# Adafruit_NeoPixel_Ring_24.net
KiCad netlist of a schematic drawn in EAGLE
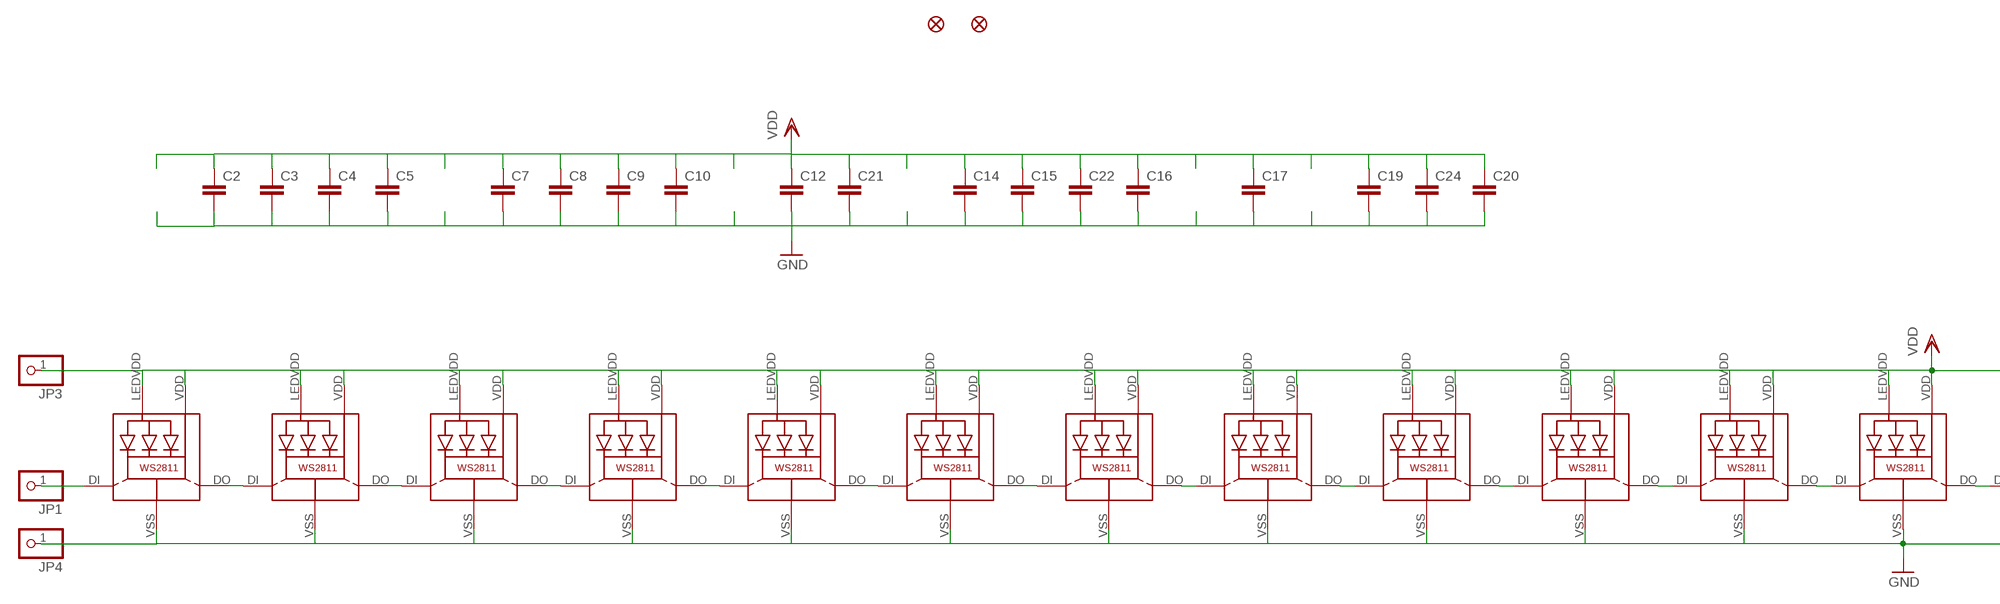
[diagram p0: schematic, sheet 1, part 1 of 2]
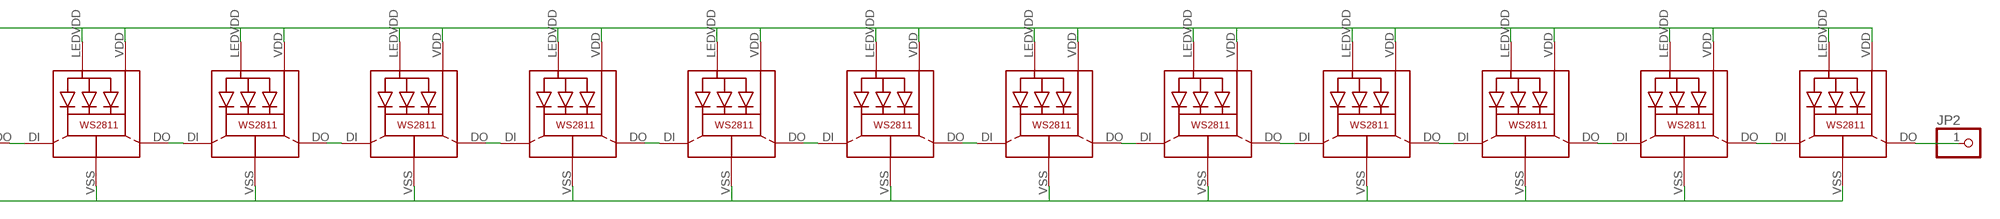
[diagram p1: schematic, sheet 1, part 2 of 2]

(export (version "E")
  (design (tool "Eeschema 10.0.6"))
  (components
    (comp (ref "C2")
      (value "C-EUC0603")
      (footprint "eagle-import:C0603")
      (libsource (lib "eagle-import") (part "C-EUC0603"))
    )
    (comp (ref "C3")
      (value "C-EUC0603")
      (footprint "eagle-import:C0603")
      (libsource (lib "eagle-import") (part "C-EUC0603"))
    )
    (comp (ref "C4")
      (value "C-EUC0603")
      (footprint "eagle-import:C0603")
      (libsource (lib "eagle-import") (part "C-EUC0603"))
    )
    (comp (ref "C5")
      (value "C-EUC0603")
      (footprint "eagle-import:C0603")
      (libsource (lib "eagle-import") (part "C-EUC0603"))
    )
    (comp (ref "C7")
      (value "C-EUC0603")
      (footprint "eagle-import:C0603")
      (libsource (lib "eagle-import") (part "C-EUC0603"))
    )
    (comp (ref "C8")
      (value "C-EUC0603")
      (footprint "eagle-import:C0603")
      (libsource (lib "eagle-import") (part "C-EUC0603"))
    )
    (comp (ref "C9")
      (value "C-EUC0603")
      (footprint "eagle-import:C0603")
      (libsource (lib "eagle-import") (part "C-EUC0603"))
    )
    (comp (ref "C10")
      (value "C-EUC0603")
      (footprint "eagle-import:C0603")
      (libsource (lib "eagle-import") (part "C-EUC0603"))
    )
    (comp (ref "C12")
      (value "C-EUC0603")
      (footprint "eagle-import:C0603")
      (libsource (lib "eagle-import") (part "C-EUC0603"))
    )
    (comp (ref "C14")
      (value "C-EUC0603")
      (footprint "eagle-import:C0603")
      (libsource (lib "eagle-import") (part "C-EUC0603"))
    )
    (comp (ref "C15")
      (value "C-EUC0603")
      (footprint "eagle-import:C0603")
      (libsource (lib "eagle-import") (part "C-EUC0603"))
    )
    (comp (ref "C16")
      (value "C-EUC0603")
      (footprint "eagle-import:C0603")
      (libsource (lib "eagle-import") (part "C-EUC0603"))
    )
    (comp (ref "C17")
      (value "C-EUC0603")
      (footprint "eagle-import:C0603")
      (libsource (lib "eagle-import") (part "C-EUC0603"))
    )
    (comp (ref "C19")
      (value "C-EUC0603")
      (footprint "eagle-import:C0603")
      (libsource (lib "eagle-import") (part "C-EUC0603"))
    )
    (comp (ref "C20")
      (value "C-EUC0603")
      (footprint "eagle-import:C0603")
      (libsource (lib "eagle-import") (part "C-EUC0603"))
    )
    (comp (ref "C21")
      (value "C-EUC0603")
      (footprint "eagle-import:C0603")
      (libsource (lib "eagle-import") (part "C-EUC0603"))
    )
    (comp (ref "C22")
      (value "C-EUC0603")
      (footprint "eagle-import:C0603")
      (libsource (lib "eagle-import") (part "C-EUC0603"))
    )
    (comp (ref "C24")
      (value "C-EUC0603")
      (footprint "eagle-import:C0603")
      (libsource (lib "eagle-import") (part "C-EUC0603"))
    )
    (comp (ref "FID1")
      (value "FIDUCIAL\"\"")
      (footprint "eagle-import:FIDUCIAL_1MM")
      (libsource (lib "eagle-import") (part "FIDUCIAL{dblquote}{dblquote}"))
    )
    (comp (ref "FID2")
      (value "FIDUCIAL\"\"")
      (footprint "eagle-import:FIDUCIAL_1MM")
      (libsource (lib "eagle-import") (part "FIDUCIAL{dblquote}{dblquote}"))
    )
    (comp (ref "JP1")
      (value "PINHD-1X1CB")
      (footprint "eagle-import:1X01-CLEANBIG")
      (libsource (lib "eagle-import") (part "PINHD-1X1CB"))
    )
    (comp (ref "JP2")
      (value "PINHD-1X1CB")
      (footprint "eagle-import:1X01-CLEANBIG")
      (libsource (lib "eagle-import") (part "PINHD-1X1CB"))
    )
    (comp (ref "JP3")
      (value "PINHD-1X1CB")
      (footprint "eagle-import:1X01-CLEANBIG")
      (libsource (lib "eagle-import") (part "PINHD-1X1CB"))
    )
    (comp (ref "JP4")
      (value "PINHD-1X1CB")
      (footprint "eagle-import:1X01-CLEANBIG")
      (libsource (lib "eagle-import") (part "PINHD-1X1CB"))
    )
    (comp (ref "LED1")
      (value "WS28115050")
      (footprint "eagle-import:WS28115050")
      (libsource (lib "eagle-import") (part "WS28115050"))
    )
    (comp (ref "LED2")
      (value "WS28115050")
      (footprint "eagle-import:WS28115050")
      (libsource (lib "eagle-import") (part "WS28115050"))
    )
    (comp (ref "LED3")
      (value "WS28115050")
      (footprint "eagle-import:WS28115050")
      (libsource (lib "eagle-import") (part "WS28115050"))
    )
    (comp (ref "LED4")
      (value "WS28115050")
      (footprint "eagle-import:WS28115050")
      (libsource (lib "eagle-import") (part "WS28115050"))
    )
    (comp (ref "LED5")
      (value "WS28115050")
      (footprint "eagle-import:WS28115050")
      (libsource (lib "eagle-import") (part "WS28115050"))
    )
    (comp (ref "LED6")
      (value "WS28115050")
      (footprint "eagle-import:WS28115050")
      (libsource (lib "eagle-import") (part "WS28115050"))
    )
    (comp (ref "LED7")
      (value "WS28115050")
      (footprint "eagle-import:WS28115050")
      (libsource (lib "eagle-import") (part "WS28115050"))
    )
    (comp (ref "LED8")
      (value "WS28115050")
      (footprint "eagle-import:WS28115050")
      (libsource (lib "eagle-import") (part "WS28115050"))
    )
    (comp (ref "LED9")
      (value "WS28115050")
      (footprint "eagle-import:WS28115050")
      (libsource (lib "eagle-import") (part "WS28115050"))
    )
    (comp (ref "LED10")
      (value "WS28115050")
      (footprint "eagle-import:WS28115050")
      (libsource (lib "eagle-import") (part "WS28115050"))
    )
    (comp (ref "LED11")
      (value "WS28115050")
      (footprint "eagle-import:WS28115050")
      (libsource (lib "eagle-import") (part "WS28115050"))
    )
    (comp (ref "LED12")
      (value "WS28115050")
      (footprint "eagle-import:WS28115050")
      (libsource (lib "eagle-import") (part "WS28115050"))
    )
    (comp (ref "LED13")
      (value "WS28115050")
      (footprint "eagle-import:WS28115050")
      (libsource (lib "eagle-import") (part "WS28115050"))
    )
    (comp (ref "LED14")
      (value "WS28115050")
      (footprint "eagle-import:WS28115050")
      (libsource (lib "eagle-import") (part "WS28115050"))
    )
    (comp (ref "LED15")
      (value "WS28115050")
      (footprint "eagle-import:WS28115050")
      (libsource (lib "eagle-import") (part "WS28115050"))
    )
    (comp (ref "LED16")
      (value "WS28115050")
      (footprint "eagle-import:WS28115050")
      (libsource (lib "eagle-import") (part "WS28115050"))
    )
    (comp (ref "LED17")
      (value "WS28115050")
      (footprint "eagle-import:WS28115050")
      (libsource (lib "eagle-import") (part "WS28115050"))
    )
    (comp (ref "LED18")
      (value "WS28115050")
      (footprint "eagle-import:WS28115050")
      (libsource (lib "eagle-import") (part "WS28115050"))
    )
    (comp (ref "LED19")
      (value "WS28115050")
      (footprint "eagle-import:WS28115050")
      (libsource (lib "eagle-import") (part "WS28115050"))
    )
    (comp (ref "LED20")
      (value "WS28115050")
      (footprint "eagle-import:WS28115050")
      (libsource (lib "eagle-import") (part "WS28115050"))
    )
    (comp (ref "LED21")
      (value "WS28115050")
      (footprint "eagle-import:WS28115050")
      (libsource (lib "eagle-import") (part "WS28115050"))
    )
    (comp (ref "LED22")
      (value "WS28115050")
      (footprint "eagle-import:WS28115050")
      (libsource (lib "eagle-import") (part "WS28115050"))
    )
    (comp (ref "LED23")
      (value "WS28115050")
      (footprint "eagle-import:WS28115050")
      (libsource (lib "eagle-import") (part "WS28115050"))
    )
    (comp (ref "LED24")
      (value "WS28115050")
      (footprint "eagle-import:WS28115050")
      (libsource (lib "eagle-import") (part "WS28115050"))
    )
  )
  (nets
    (net (code "1") (name "GND") (class "Default")
      (node (ref "C10") (pin "2") (pinfunction "2_2") (pintype "passive"))
      (node (ref "C12") (pin "2") (pinfunction "2_2") (pintype "passive"))
      (node (ref "C14") (pin "2") (pinfunction "2_2") (pintype "passive"))
      (node (ref "C15") (pin "2") (pinfunction "2_2") (pintype "passive"))
      (node (ref "C16") (pin "2") (pinfunction "2_2") (pintype "passive"))
      (node (ref "C17") (pin "2") (pinfunction "2_2") (pintype "passive"))
      (node (ref "C19") (pin "2") (pinfunction "2_2") (pintype "passive"))
      (node (ref "C2") (pin "2") (pinfunction "2_2") (pintype "passive"))
      (node (ref "C20") (pin "2") (pinfunction "2_2") (pintype "passive"))
      (node (ref "C21") (pin "2") (pinfunction "2_2") (pintype "passive"))
      (node (ref "C22") (pin "2") (pinfunction "2_2") (pintype "passive"))
      (node (ref "C24") (pin "2") (pinfunction "2_2") (pintype "passive"))
      (node (ref "C3") (pin "2") (pinfunction "2_2") (pintype "passive"))
      (node (ref "C4") (pin "2") (pinfunction "2_2") (pintype "passive"))
      (node (ref "C5") (pin "2") (pinfunction "2_2") (pintype "passive"))
      (node (ref "C7") (pin "2") (pinfunction "2_2") (pintype "passive"))
      (node (ref "C8") (pin "2") (pinfunction "2_2") (pintype "passive"))
      (node (ref "C9") (pin "2") (pinfunction "2_2") (pintype "passive"))
      (node (ref "JP4") (pin "1") (pinfunction "1_1") (pintype "passive"))
      (node (ref "LED1") (pin "VSS") (pinfunction "GND_VSS") (pintype "power_in"))
      (node (ref "LED10") (pin "VSS") (pinfunction "GND_VSS") (pintype "power_in"))
      (node (ref "LED11") (pin "VSS") (pinfunction "GND_VSS") (pintype "power_in"))
      (node (ref "LED12") (pin "VSS") (pinfunction "GND_VSS") (pintype "power_in"))
      (node (ref "LED13") (pin "VSS") (pinfunction "GND_VSS") (pintype "power_in"))
      (node (ref "LED14") (pin "VSS") (pinfunction "GND_VSS") (pintype "power_in"))
      (node (ref "LED15") (pin "VSS") (pinfunction "GND_VSS") (pintype "power_in"))
      (node (ref "LED16") (pin "VSS") (pinfunction "GND_VSS") (pintype "power_in"))
      (node (ref "LED17") (pin "VSS") (pinfunction "GND_VSS") (pintype "power_in"))
      (node (ref "LED18") (pin "VSS") (pinfunction "GND_VSS") (pintype "power_in"))
      (node (ref "LED19") (pin "VSS") (pinfunction "GND_VSS") (pintype "power_in"))
      (node (ref "LED2") (pin "VSS") (pinfunction "GND_VSS") (pintype "power_in"))
      (node (ref "LED20") (pin "VSS") (pinfunction "GND_VSS") (pintype "power_in"))
      (node (ref "LED21") (pin "VSS") (pinfunction "GND_VSS") (pintype "power_in"))
      (node (ref "LED22") (pin "VSS") (pinfunction "GND_VSS") (pintype "power_in"))
      (node (ref "LED23") (pin "VSS") (pinfunction "GND_VSS") (pintype "power_in"))
      (node (ref "LED24") (pin "VSS") (pinfunction "GND_VSS") (pintype "power_in"))
      (node (ref "LED3") (pin "VSS") (pinfunction "GND_VSS") (pintype "power_in"))
      (node (ref "LED4") (pin "VSS") (pinfunction "GND_VSS") (pintype "power_in"))
      (node (ref "LED5") (pin "VSS") (pinfunction "GND_VSS") (pintype "power_in"))
      (node (ref "LED6") (pin "VSS") (pinfunction "GND_VSS") (pintype "power_in"))
      (node (ref "LED7") (pin "VSS") (pinfunction "GND_VSS") (pintype "power_in"))
      (node (ref "LED8") (pin "VSS") (pinfunction "GND_VSS") (pintype "power_in"))
      (node (ref "LED9") (pin "VSS") (pinfunction "GND_VSS") (pintype "power_in"))
    )
    (net (code "2") (name "Net-(JP1-Pad1)") (class "Default")
      (node (ref "JP1") (pin "1") (pinfunction "1_1") (pintype "passive"))
      (node (ref "LED1") (pin "DI") (pinfunction "DI_DI") (pintype "input"))
    )
    (net (code "3") (name "Net-(JP2-Pad1)") (class "Default")
      (node (ref "JP2") (pin "1") (pinfunction "1_1") (pintype "passive"))
      (node (ref "LED24") (pin "DO") (pinfunction "DO_DO") (pintype "output"))
    )
    (net (code "4") (name "Net-(LED1-PadDO)") (class "Default")
      (node (ref "LED1") (pin "DO") (pinfunction "DO_DO") (pintype "output"))
      (node (ref "LED2") (pin "DI") (pinfunction "DI_DI") (pintype "input"))
    )
    (net (code "5") (name "Net-(LED2-PadDO)") (class "Default")
      (node (ref "LED2") (pin "DO") (pinfunction "DO_DO") (pintype "output"))
      (node (ref "LED3") (pin "DI") (pinfunction "DI_DI") (pintype "input"))
    )
    (net (code "6") (name "Net-(LED3-PadDO)") (class "Default")
      (node (ref "LED3") (pin "DO") (pinfunction "DO_DO") (pintype "output"))
      (node (ref "LED4") (pin "DI") (pinfunction "DI_DI") (pintype "input"))
    )
    (net (code "7") (name "Net-(LED4-PadDO)") (class "Default")
      (node (ref "LED4") (pin "DO") (pinfunction "DO_DO") (pintype "output"))
      (node (ref "LED5") (pin "DI") (pinfunction "DI_DI") (pintype "input"))
    )
    (net (code "8") (name "Net-(LED5-PadDO)") (class "Default")
      (node (ref "LED5") (pin "DO") (pinfunction "DO_DO") (pintype "output"))
      (node (ref "LED6") (pin "DI") (pinfunction "DI_DI") (pintype "input"))
    )
    (net (code "9") (name "Net-(LED6-PadDO)") (class "Default")
      (node (ref "LED6") (pin "DO") (pinfunction "DO_DO") (pintype "output"))
      (node (ref "LED7") (pin "DI") (pinfunction "DI_DI") (pintype "input"))
    )
    (net (code "10") (name "Net-(LED7-PadDO)") (class "Default")
      (node (ref "LED7") (pin "DO") (pinfunction "DO_DO") (pintype "output"))
      (node (ref "LED8") (pin "DI") (pinfunction "DI_DI") (pintype "input"))
    )
    (net (code "11") (name "Net-(LED8-PadDO)") (class "Default")
      (node (ref "LED8") (pin "DO") (pinfunction "DO_DO") (pintype "output"))
      (node (ref "LED9") (pin "DI") (pinfunction "DI_DI") (pintype "input"))
    )
    (net (code "12") (name "Net-(LED10-PadDI)") (class "Default")
      (node (ref "LED10") (pin "DI") (pinfunction "DI_DI") (pintype "input"))
      (node (ref "LED9") (pin "DO") (pinfunction "DO_DO") (pintype "output"))
    )
    (net (code "13") (name "Net-(LED10-PadDO)") (class "Default")
      (node (ref "LED10") (pin "DO") (pinfunction "DO_DO") (pintype "output"))
      (node (ref "LED11") (pin "DI") (pinfunction "DI_DI") (pintype "input"))
    )
    (net (code "14") (name "Net-(LED11-PadDO)") (class "Default")
      (node (ref "LED11") (pin "DO") (pinfunction "DO_DO") (pintype "output"))
      (node (ref "LED12") (pin "DI") (pinfunction "DI_DI") (pintype "input"))
    )
    (net (code "15") (name "Net-(LED12-PadDO)") (class "Default")
      (node (ref "LED12") (pin "DO") (pinfunction "DO_DO") (pintype "output"))
      (node (ref "LED13") (pin "DI") (pinfunction "DI_DI") (pintype "input"))
    )
    (net (code "16") (name "Net-(LED13-PadDO)") (class "Default")
      (node (ref "LED13") (pin "DO") (pinfunction "DO_DO") (pintype "output"))
      (node (ref "LED14") (pin "DI") (pinfunction "DI_DI") (pintype "input"))
    )
    (net (code "17") (name "Net-(LED14-PadDO)") (class "Default")
      (node (ref "LED14") (pin "DO") (pinfunction "DO_DO") (pintype "output"))
      (node (ref "LED15") (pin "DI") (pinfunction "DI_DI") (pintype "input"))
    )
    (net (code "18") (name "Net-(LED15-PadDO)") (class "Default")
      (node (ref "LED15") (pin "DO") (pinfunction "DO_DO") (pintype "output"))
      (node (ref "LED16") (pin "DI") (pinfunction "DI_DI") (pintype "input"))
    )
    (net (code "19") (name "Net-(LED16-PadDO)") (class "Default")
      (node (ref "LED16") (pin "DO") (pinfunction "DO_DO") (pintype "output"))
      (node (ref "LED17") (pin "DI") (pinfunction "DI_DI") (pintype "input"))
    )
    (net (code "20") (name "Net-(LED17-PadDO)") (class "Default")
      (node (ref "LED17") (pin "DO") (pinfunction "DO_DO") (pintype "output"))
      (node (ref "LED18") (pin "DI") (pinfunction "DI_DI") (pintype "input"))
    )
    (net (code "21") (name "Net-(LED18-PadDO)") (class "Default")
      (node (ref "LED18") (pin "DO") (pinfunction "DO_DO") (pintype "output"))
      (node (ref "LED19") (pin "DI") (pinfunction "DI_DI") (pintype "input"))
    )
    (net (code "22") (name "Net-(LED19-PadDO)") (class "Default")
      (node (ref "LED19") (pin "DO") (pinfunction "DO_DO") (pintype "output"))
      (node (ref "LED20") (pin "DI") (pinfunction "DI_DI") (pintype "input"))
    )
    (net (code "23") (name "Net-(LED20-PadDO)") (class "Default")
      (node (ref "LED20") (pin "DO") (pinfunction "DO_DO") (pintype "output"))
      (node (ref "LED21") (pin "DI") (pinfunction "DI_DI") (pintype "input"))
    )
    (net (code "24") (name "Net-(LED21-PadDO)") (class "Default")
      (node (ref "LED21") (pin "DO") (pinfunction "DO_DO") (pintype "output"))
      (node (ref "LED22") (pin "DI") (pinfunction "DI_DI") (pintype "input"))
    )
    (net (code "25") (name "Net-(LED22-PadDO)") (class "Default")
      (node (ref "LED22") (pin "DO") (pinfunction "DO_DO") (pintype "output"))
      (node (ref "LED23") (pin "DI") (pinfunction "DI_DI") (pintype "input"))
    )
    (net (code "26") (name "Net-(LED23-PadDO)") (class "Default")
      (node (ref "LED23") (pin "DO") (pinfunction "DO_DO") (pintype "output"))
      (node (ref "LED24") (pin "DI") (pinfunction "DI_DI") (pintype "input"))
    )
    (net (code "27") (name "VDD") (class "Default")
      (node (ref "C10") (pin "1") (pinfunction "1_1") (pintype "passive"))
      (node (ref "C12") (pin "1") (pinfunction "1_1") (pintype "passive"))
      (node (ref "C14") (pin "1") (pinfunction "1_1") (pintype "passive"))
      (node (ref "C15") (pin "1") (pinfunction "1_1") (pintype "passive"))
      (node (ref "C16") (pin "1") (pinfunction "1_1") (pintype "passive"))
      (node (ref "C17") (pin "1") (pinfunction "1_1") (pintype "passive"))
      (node (ref "C19") (pin "1") (pinfunction "1_1") (pintype "passive"))
      (node (ref "C2") (pin "1") (pinfunction "1_1") (pintype "passive"))
      (node (ref "C20") (pin "1") (pinfunction "1_1") (pintype "passive"))
      (node (ref "C21") (pin "1") (pinfunction "1_1") (pintype "passive"))
      (node (ref "C22") (pin "1") (pinfunction "1_1") (pintype "passive"))
      (node (ref "C24") (pin "1") (pinfunction "1_1") (pintype "passive"))
      (node (ref "C3") (pin "1") (pinfunction "1_1") (pintype "passive"))
      (node (ref "C4") (pin "1") (pinfunction "1_1") (pintype "passive"))
      (node (ref "C5") (pin "1") (pinfunction "1_1") (pintype "passive"))
      (node (ref "C7") (pin "1") (pinfunction "1_1") (pintype "passive"))
      (node (ref "C8") (pin "1") (pinfunction "1_1") (pintype "passive"))
      (node (ref "C9") (pin "1") (pinfunction "1_1") (pintype "passive"))
      (node (ref "JP3") (pin "1") (pinfunction "1_1") (pintype "passive"))
      (node (ref "LED1") (pin "LEDVDD") (pinfunction "LEDVDD_LEDVDD") (pintype "power_in"))
      (node (ref "LED1") (pin "VDD") (pinfunction "VDD_VDD") (pintype "power_in"))
      (node (ref "LED10") (pin "LEDVDD") (pinfunction "LEDVDD_LEDVDD") (pintype "power_in"))
      (node (ref "LED10") (pin "VDD") (pinfunction "VDD_VDD") (pintype "power_in"))
      (node (ref "LED11") (pin "LEDVDD") (pinfunction "LEDVDD_LEDVDD") (pintype "power_in"))
      (node (ref "LED11") (pin "VDD") (pinfunction "VDD_VDD") (pintype "power_in"))
      (node (ref "LED12") (pin "LEDVDD") (pinfunction "LEDVDD_LEDVDD") (pintype "power_in"))
      (node (ref "LED12") (pin "VDD") (pinfunction "VDD_VDD") (pintype "power_in"))
      (node (ref "LED13") (pin "LEDVDD") (pinfunction "LEDVDD_LEDVDD") (pintype "power_in"))
      (node (ref "LED13") (pin "VDD") (pinfunction "VDD_VDD") (pintype "power_in"))
      (node (ref "LED14") (pin "LEDVDD") (pinfunction "LEDVDD_LEDVDD") (pintype "power_in"))
      (node (ref "LED14") (pin "VDD") (pinfunction "VDD_VDD") (pintype "power_in"))
      (node (ref "LED15") (pin "LEDVDD") (pinfunction "LEDVDD_LEDVDD") (pintype "power_in"))
      (node (ref "LED15") (pin "VDD") (pinfunction "VDD_VDD") (pintype "power_in"))
      (node (ref "LED16") (pin "LEDVDD") (pinfunction "LEDVDD_LEDVDD") (pintype "power_in"))
      (node (ref "LED16") (pin "VDD") (pinfunction "VDD_VDD") (pintype "power_in"))
      (node (ref "LED17") (pin "LEDVDD") (pinfunction "LEDVDD_LEDVDD") (pintype "power_in"))
      (node (ref "LED17") (pin "VDD") (pinfunction "VDD_VDD") (pintype "power_in"))
      (node (ref "LED18") (pin "LEDVDD") (pinfunction "LEDVDD_LEDVDD") (pintype "power_in"))
      (node (ref "LED18") (pin "VDD") (pinfunction "VDD_VDD") (pintype "power_in"))
      (node (ref "LED19") (pin "LEDVDD") (pinfunction "LEDVDD_LEDVDD") (pintype "power_in"))
      (node (ref "LED19") (pin "VDD") (pinfunction "VDD_VDD") (pintype "power_in"))
      (node (ref "LED2") (pin "LEDVDD") (pinfunction "LEDVDD_LEDVDD") (pintype "power_in"))
      (node (ref "LED2") (pin "VDD") (pinfunction "VDD_VDD") (pintype "power_in"))
      (node (ref "LED20") (pin "LEDVDD") (pinfunction "LEDVDD_LEDVDD") (pintype "power_in"))
      (node (ref "LED20") (pin "VDD") (pinfunction "VDD_VDD") (pintype "power_in"))
      (node (ref "LED21") (pin "LEDVDD") (pinfunction "LEDVDD_LEDVDD") (pintype "power_in"))
      (node (ref "LED21") (pin "VDD") (pinfunction "VDD_VDD") (pintype "power_in"))
      (node (ref "LED22") (pin "LEDVDD") (pinfunction "LEDVDD_LEDVDD") (pintype "power_in"))
      (node (ref "LED22") (pin "VDD") (pinfunction "VDD_VDD") (pintype "power_in"))
      (node (ref "LED23") (pin "LEDVDD") (pinfunction "LEDVDD_LEDVDD") (pintype "power_in"))
      (node (ref "LED23") (pin "VDD") (pinfunction "VDD_VDD") (pintype "power_in"))
      (node (ref "LED24") (pin "LEDVDD") (pinfunction "LEDVDD_LEDVDD") (pintype "power_in"))
      (node (ref "LED24") (pin "VDD") (pinfunction "VDD_VDD") (pintype "power_in"))
      (node (ref "LED3") (pin "LEDVDD") (pinfunction "LEDVDD_LEDVDD") (pintype "power_in"))
      (node (ref "LED3") (pin "VDD") (pinfunction "VDD_VDD") (pintype "power_in"))
      (node (ref "LED4") (pin "LEDVDD") (pinfunction "LEDVDD_LEDVDD") (pintype "power_in"))
      (node (ref "LED4") (pin "VDD") (pinfunction "VDD_VDD") (pintype "power_in"))
      (node (ref "LED5") (pin "LEDVDD") (pinfunction "LEDVDD_LEDVDD") (pintype "power_in"))
      (node (ref "LED5") (pin "VDD") (pinfunction "VDD_VDD") (pintype "power_in"))
      (node (ref "LED6") (pin "LEDVDD") (pinfunction "LEDVDD_LEDVDD") (pintype "power_in"))
      (node (ref "LED6") (pin "VDD") (pinfunction "VDD_VDD") (pintype "power_in"))
      (node (ref "LED7") (pin "LEDVDD") (pinfunction "LEDVDD_LEDVDD") (pintype "power_in"))
      (node (ref "LED7") (pin "VDD") (pinfunction "VDD_VDD") (pintype "power_in"))
      (node (ref "LED8") (pin "LEDVDD") (pinfunction "LEDVDD_LEDVDD") (pintype "power_in"))
      (node (ref "LED8") (pin "VDD") (pinfunction "VDD_VDD") (pintype "power_in"))
      (node (ref "LED9") (pin "LEDVDD") (pinfunction "LEDVDD_LEDVDD") (pintype "power_in"))
      (node (ref "LED9") (pin "VDD") (pinfunction "VDD_VDD") (pintype "power_in"))
    )
  )
)
